# 32m1-ssm.net
KiCad netlist of a schematic drawn in Altium Designer
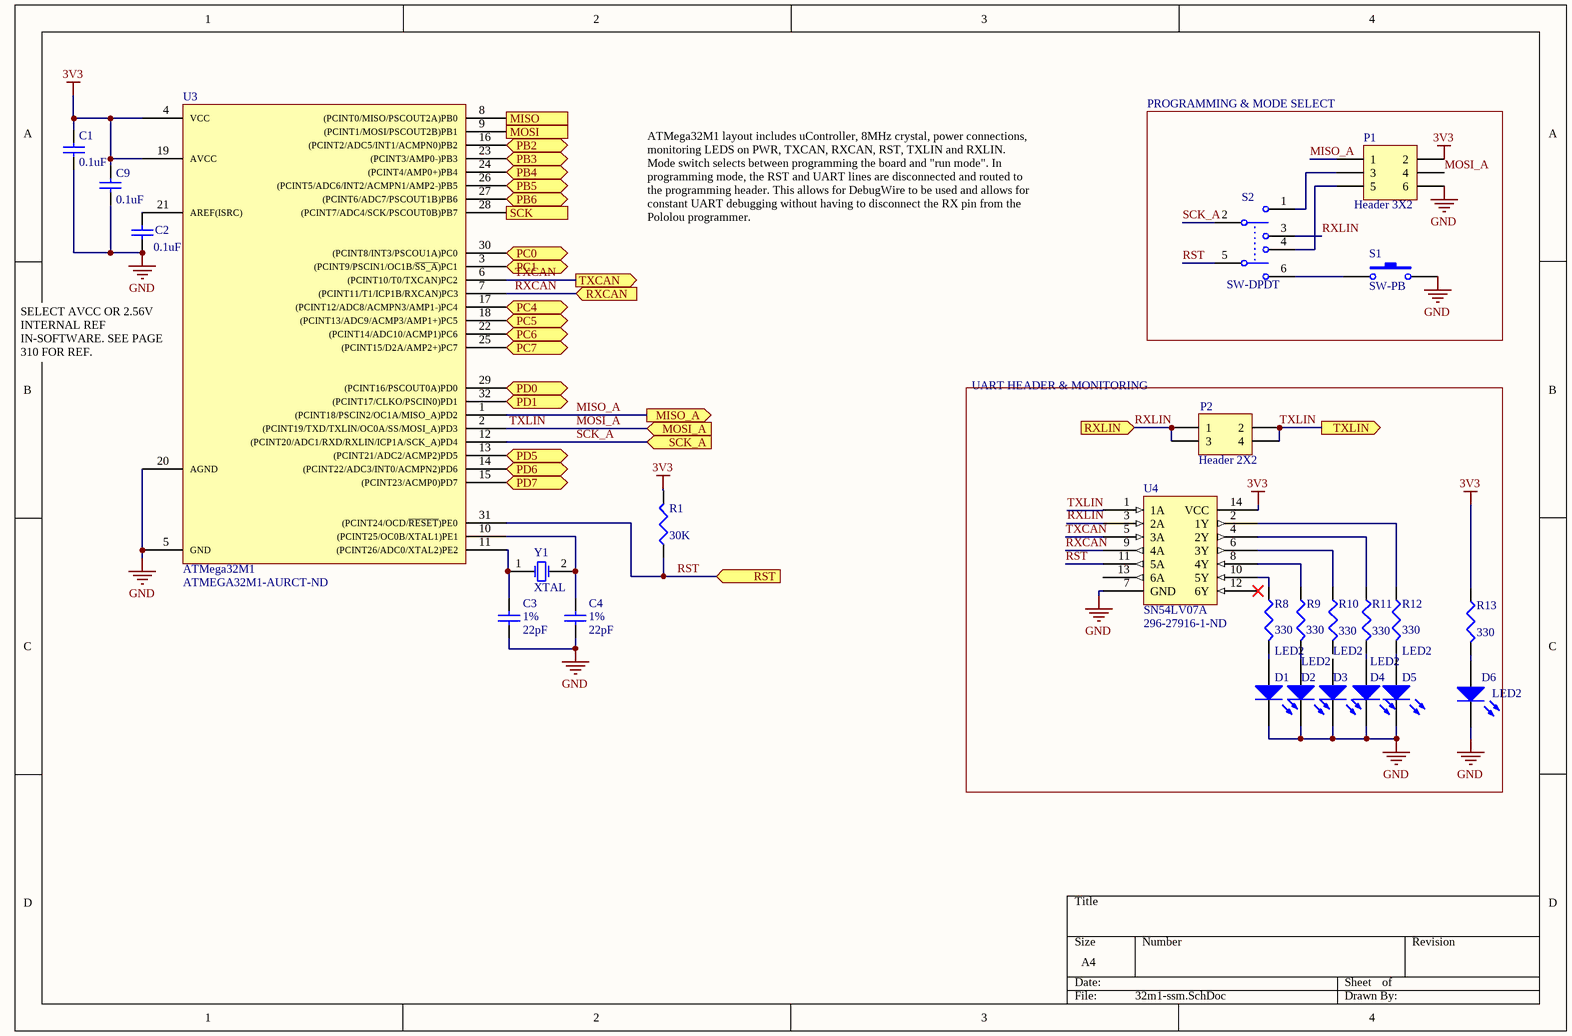
[diagram p0: 32m1-ssm.SchDoc]

(export (version "E")
  (design (tool "Eeschema 10.0.6"))
  (components
    (comp (ref "C1")
      (value "0.1uF")
      (footprint "C1206")
      (description "Capacitor (Semiconductor SIM Model)")
      (fields (field (name "Comment") "Cap Semi") (field (name "PUBLISHER") "Altium Limited"))
      (libsource (lib "Miscellaneous Devices") (part "Cap Semi"))
    )
    (comp (ref "C2")
      (value "0.1uF")
      (footprint "C1206")
      (description "Capacitor (Semiconductor SIM Model)")
      (fields (field (name "Comment") "Cap Semi") (field (name "PUBLISHER") "Altium Limited"))
      (libsource (lib "Miscellaneous Devices") (part "Cap Semi"))
    )
    (comp (ref "C3")
      (value "1%")
      (footprint "C1206")
      (description "Capacitor (Semiconductor SIM Model)")
      (fields (field (name "ALTIUM_VALUE") "22pF") (field (name "PUBLISHER") "Altium Limited"))
      (libsource (lib "Miscellaneous Devices") (part "Cap Semi"))
    )
    (comp (ref "C4")
      (value "1%")
      (footprint "C1206")
      (description "Capacitor (Semiconductor SIM Model)")
      (fields (field (name "ALTIUM_VALUE") "22pF") (field (name "PUBLISHER") "Altium Limited"))
      (libsource (lib "Miscellaneous Devices") (part "Cap Semi"))
    )
    (comp (ref "C9")
      (value "0.1uF")
      (footprint "C1206")
      (description "Capacitor (Semiconductor SIM Model)")
      (fields (field (name "Comment") "Cap Semi") (field (name "PUBLISHER") "Altium Limited"))
      (libsource (lib "Miscellaneous Devices") (part "Cap Semi"))
    )
    (comp (ref "D1")
      (value "LED2")
      (footprint "3.2X1.6X1.1")
      (description "Typical RED, GREEN, YELLOW, AMBER GaAs LED")
      (fields (field (name "PUBLISHER") "Altium Limited"))
      (libsource (lib "Miscellaneous Devices") (part "LED2"))
    )
    (comp (ref "D2")
      (value "LED2")
      (footprint "3.2X1.6X1.1")
      (description "Typical RED, GREEN, YELLOW, AMBER GaAs LED")
      (fields (field (name "PUBLISHER") "Altium Limited"))
      (libsource (lib "Miscellaneous Devices") (part "LED2"))
    )
    (comp (ref "D3")
      (value "LED2")
      (footprint "3.2X1.6X1.1")
      (description "Typical RED, GREEN, YELLOW, AMBER GaAs LED")
      (fields (field (name "PUBLISHER") "Altium Limited"))
      (libsource (lib "Miscellaneous Devices") (part "LED2"))
    )
    (comp (ref "D4")
      (value "LED2")
      (footprint "3.2X1.6X1.1")
      (description "Typical RED, GREEN, YELLOW, AMBER GaAs LED")
      (fields (field (name "PUBLISHER") "Altium Limited"))
      (libsource (lib "Miscellaneous Devices") (part "LED2"))
    )
    (comp (ref "D5")
      (value "LED2")
      (footprint "3.2X1.6X1.1")
      (description "Typical RED, GREEN, YELLOW, AMBER GaAs LED")
      (fields (field (name "PUBLISHER") "Altium Limited"))
      (libsource (lib "Miscellaneous Devices") (part "LED2"))
    )
    (comp (ref "D6")
      (value "LED2")
      (footprint "3.2X1.6X1.1")
      (description "Typical RED, GREEN, YELLOW, AMBER GaAs LED")
      (fields (field (name "PUBLISHER") "Altium Limited"))
      (libsource (lib "Miscellaneous Devices") (part "LED2"))
    )
    (comp (ref "P1")
      (value "Header 3X2")
      (footprint "HDR2X3")
      (description "Header, 3-Pin, Dual row")
      (fields (field (name "PUBLISHER") "Altium Limited"))
      (libsource (lib "Miscellaneous Connectors") (part "Header 3X2"))
    )
    (comp (ref "P2")
      (value "Header 2X2")
      (footprint "HDR2X2")
      (description "Header, 2-Pin, Dual row")
      (fields (field (name "PUBLISHER") "Altium Limited"))
      (libsource (lib "Miscellaneous Connectors") (part "Header 2X2"))
    )
    (comp (ref "R1")
      (value "30K")
      (footprint "J1-0603")
      (description "Resistor")
      (fields (field (name "Comment") "Res3") (field (name "PUBLISHER") "Altium Limited"))
      (libsource (lib "Miscellaneous Devices") (part "Res3"))
    )
    (comp (ref "R8")
      (value "330")
      (footprint "J1-0603")
      (description "Resistor")
      (fields (field (name "Comment") "Res3") (field (name "PUBLISHER") "Altium Limited"))
      (libsource (lib "Miscellaneous Devices") (part "Res3"))
    )
    (comp (ref "R9")
      (value "330")
      (footprint "J1-0603")
      (description "Resistor")
      (fields (field (name "Comment") "Res3") (field (name "PUBLISHER") "Altium Limited"))
      (libsource (lib "Miscellaneous Devices") (part "Res3"))
    )
    (comp (ref "R10")
      (value "330")
      (footprint "J1-0603")
      (description "Resistor")
      (fields (field (name "Comment") "Res3") (field (name "PUBLISHER") "Altium Limited"))
      (libsource (lib "Miscellaneous Devices") (part "Res3"))
    )
    (comp (ref "R11")
      (value "330")
      (footprint "J1-0603")
      (description "Resistor")
      (fields (field (name "Comment") "Res3") (field (name "PUBLISHER") "Altium Limited"))
      (libsource (lib "Miscellaneous Devices") (part "Res3"))
    )
    (comp (ref "R12")
      (value "330")
      (footprint "J1-0603")
      (description "Resistor")
      (fields (field (name "Comment") "Res3") (field (name "PUBLISHER") "Altium Limited"))
      (libsource (lib "Miscellaneous Devices") (part "Res3"))
    )
    (comp (ref "R13")
      (value "330")
      (footprint "J1-0603")
      (description "Resistor")
      (fields (field (name "Comment") "Res3") (field (name "PUBLISHER") "Altium Limited"))
      (libsource (lib "Miscellaneous Devices") (part "Res3"))
    )
    (comp (ref "S1")
      (value "SW-PB")
      (footprint "SPST-2")
      (description "Switch")
      (fields (field (name "PUBLISHER") "Altium Limited"))
      (libsource (lib "Miscellaneous Devices") (part "SW-PB"))
    )
    (comp (ref "S2")
      (value "SW-DPDT")
      (footprint "PCBComponent_1")
      (description "Double-Pole, Double-Throw Switch")
      (fields (field (name "PUBLISHER") "Altium Limited"))
      (libsource (lib "Miscellaneous Devices") (part "SW-DPDT"))
    )
    (comp (ref "U3")
      (value "ATMega32M1")
      (footprint "QFP80P900X900X120-32N")
      (description "Atmel 8-bit AVR microcontroller.")
      (fields (field (name "SUPPLIER PART NUMBER 1") "ATMEGA32M1-AURCT-ND"))
      (libsource (lib "ICs") (part "ATMega32M1"))
    )
    (comp (ref "U4")
      (value "SN54LV07A")
      (footprint "SOT402-1_N")
      (description "Six element 1-bit non-inverting open-drain buffer.")
      (fields (field (name "SUPPLIER PART NUMBER") "296-27916-1-ND"))
      (libsource (lib "ICs") (part "SN54LV07A"))
    )
    (comp (ref "Y1")
      (value "XTAL")
      (footprint "R38")
      (description "Crystal Oscillator")
      (fields (field (name "PUBLISHER") "Altium Limited"))
      (libsource (lib "Miscellaneous Devices") (part "XTAL"))
    )
  )
  (nets
    (net (code "1") (name "/MISO") (class "Default")
      (node (ref "U3") (pin "8") (pinfunction "(PCINT0/MISO/PSCOUT2A)PB0_8") (pintype "passive"))
    )
    (net (code "2") (name "/MISO_A") (class "Default")
      (node (ref "P1") (pin "1") (pinfunction "1_1") (pintype "passive"))
      (node (ref "U3") (pin "1") (pinfunction "(PCINT18/PSCIN2/OC1A/MISO_A)PD2_1") (pintype "passive"))
    )
    (net (code "3") (name "/MOSI") (class "Default")
      (node (ref "U3") (pin "9") (pinfunction "(PCINT1/MOSI/PSCOUT2B)PB1_9") (pintype "passive"))
    )
    (net (code "4") (name "/MOSI_A") (class "Default")
      (node (ref "P1") (pin "4") (pinfunction "4_4") (pintype "passive"))
      (node (ref "P2") (pin "2") (pinfunction "2_2") (pintype "passive"))
      (node (ref "P2") (pin "4") (pinfunction "4_4") (pintype "passive"))
      (node (ref "U3") (pin "2") (pinfunction "(PCINT19/TXD/TXLIN/OC0A/SS/MOSI_A)PD3_2") (pintype "passive"))
      (node (ref "U4") (pin "1") (pinfunction "1A_1") (pintype "input"))
    )
    (net (code "5") (name "/PB2") (class "Default")
      (node (ref "U3") (pin "16") (pinfunction "(PCINT2/ADC5/INT1/ACMPN0)PB2_16") (pintype "passive"))
    )
    (net (code "6") (name "/PB3") (class "Default")
      (node (ref "U3") (pin "23") (pinfunction "(PCINT3/AMP0-)PB3_23") (pintype "passive"))
    )
    (net (code "7") (name "/PB4") (class "Default")
      (node (ref "U3") (pin "24") (pinfunction "(PCINT4/AMP0+)PB4_24") (pintype "passive"))
    )
    (net (code "8") (name "/PB5") (class "Default")
      (node (ref "U3") (pin "26") (pinfunction "(PCINT5/ADC6/INT2/ACMPN1/AMP2-)PB5_26") (pintype "passive"))
    )
    (net (code "9") (name "/PB6") (class "Default")
      (node (ref "U3") (pin "27") (pinfunction "(PCINT6/ADC7/PSCOUT1B)PB6_27") (pintype "passive"))
    )
    (net (code "10") (name "/PC0") (class "Default")
      (node (ref "U3") (pin "30") (pinfunction "(PCINT8/INT3/PSCOU1A)PC0_30") (pintype "passive"))
    )
    (net (code "11") (name "/PC1") (class "Default")
      (node (ref "U3") (pin "3") (pinfunction "(PCINT9/PSCIN1/OC1B/~{SS_A})PC1_3") (pintype "passive"))
    )
    (net (code "12") (name "/PC4") (class "Default")
      (node (ref "U3") (pin "17") (pinfunction "(PCINT12/ADC8/ACMPN3/AMP1-)PC4_17") (pintype "passive"))
    )
    (net (code "13") (name "/PC5") (class "Default")
      (node (ref "U3") (pin "18") (pinfunction "(PCINT13/ADC9/ACMP3/AMP1+)PC5_18") (pintype "passive"))
    )
    (net (code "14") (name "/PC6") (class "Default")
      (node (ref "U3") (pin "22") (pinfunction "(PCINT14/ADC10/ACMP1)PC6_22") (pintype "passive"))
    )
    (net (code "15") (name "/PC7") (class "Default")
      (node (ref "U3") (pin "25") (pinfunction "(PCINT15/D2A/AMP2+)PC7_25") (pintype "passive"))
    )
    (net (code "16") (name "/PD0") (class "Default")
      (node (ref "U3") (pin "29") (pinfunction "(PCINT16/PSCOUT0A)PD0_29") (pintype "passive"))
    )
    (net (code "17") (name "/PD1") (class "Default")
      (node (ref "U3") (pin "32") (pinfunction "(PCINT17/CLKO/PSCIN0)PD1_32") (pintype "passive"))
    )
    (net (code "18") (name "/PD5") (class "Default")
      (node (ref "U3") (pin "13") (pinfunction "(PCINT21/ADC2/ACMP2)PD5_13") (pintype "passive"))
    )
    (net (code "19") (name "/PD6") (class "Default")
      (node (ref "U3") (pin "14") (pinfunction "(PCINT22/ADC3/INT0/ACMPN2)PD6_14") (pintype "passive"))
    )
    (net (code "20") (name "/PD7") (class "Default")
      (node (ref "U3") (pin "15") (pinfunction "(PCINT23/ACMP0)PD7_15") (pintype "passive"))
    )
    (net (code "21") (name "/RST") (class "Default")
      (node (ref "R1") (pin "1") (pinfunction "1_1") (pintype "passive"))
      (node (ref "S2") (pin "5") (pinfunction "5_5") (pintype "passive"))
      (node (ref "U3") (pin "31") (pinfunction "(PCINT24/OCD/~{RESET})PE0_31") (pintype "passive"))
      (node (ref "U4") (pin "11") (pinfunction "5A_11") (pintype "output"))
    )
    (net (code "22") (name "/RXCAN") (class "Default")
      (node (ref "U3") (pin "7") (pinfunction "(PCINT11/T1/ICP1B/RXCAN)PC3_7") (pintype "passive"))
      (node (ref "U4") (pin "9") (pinfunction "4A_9") (pintype "output"))
    )
    (net (code "23") (name "/RXLIN") (class "Default")
      (node (ref "P2") (pin "1") (pinfunction "1_1") (pintype "passive"))
      (node (ref "P2") (pin "3") (pinfunction "3_3") (pintype "passive"))
      (node (ref "S2") (pin "3") (pinfunction "3_3") (pintype "passive"))
      (node (ref "U4") (pin "3") (pinfunction "2A_3") (pintype "input"))
    )
    (net (code "24") (name "/SCK") (class "Default")
      (node (ref "U3") (pin "28") (pinfunction "(PCINT7/ADC4/SCK/PSCOUT0B)PB7_28") (pintype "passive"))
    )
    (net (code "25") (name "/SCK_A") (class "Default")
      (node (ref "S2") (pin "2") (pinfunction "2_2") (pintype "passive"))
      (node (ref "U3") (pin "12") (pinfunction "(PCINT20/ADC1/RXD/RXLIN/ICP1A/SCK_A)PD4_12") (pintype "passive"))
    )
    (net (code "26") (name "/TXCAN") (class "Default")
      (node (ref "U3") (pin "6") (pinfunction "(PCINT10/T0/TXCAN)PC2_6") (pintype "passive"))
      (node (ref "U4") (pin "5") (pinfunction "3A_5") (pintype "input"))
    )
    (net (code "27") (name "3V3") (class "Default")
      (node (ref "C1") (pin "2") (pinfunction "2_2") (pintype "passive"))
      (node (ref "C9") (pin "2") (pinfunction "2_2") (pintype "passive"))
      (node (ref "P1") (pin "2") (pinfunction "2_2") (pintype "passive"))
      (node (ref "R1") (pin "2") (pinfunction "2_2") (pintype "passive"))
      (node (ref "R13") (pin "1") (pinfunction "1_1") (pintype "passive"))
      (node (ref "U3") (pin "19") (pinfunction "AVCC_19") (pintype "passive"))
      (node (ref "U3") (pin "4") (pinfunction "VCC_4") (pintype "passive"))
      (node (ref "U4") (pin "14") (pinfunction "VCC_14") (pintype "power_in"))
    )
    (net (code "28") (name "GND") (class "Default")
      (node (ref "C1") (pin "1") (pinfunction "1_1") (pintype "passive"))
      (node (ref "C2") (pin "2") (pinfunction "2_2") (pintype "passive"))
      (node (ref "C3") (pin "1") (pinfunction "1_1") (pintype "passive"))
      (node (ref "C4") (pin "1") (pinfunction "1_1") (pintype "passive"))
      (node (ref "C9") (pin "1") (pinfunction "1_1") (pintype "passive"))
      (node (ref "D1") (pin "2") (pinfunction "K_2") (pintype "passive"))
      (node (ref "D2") (pin "2") (pinfunction "K_2") (pintype "passive"))
      (node (ref "D3") (pin "2") (pinfunction "K_2") (pintype "passive"))
      (node (ref "D4") (pin "2") (pinfunction "K_2") (pintype "passive"))
      (node (ref "D5") (pin "2") (pinfunction "K_2") (pintype "passive"))
      (node (ref "D6") (pin "2") (pinfunction "K_2") (pintype "passive"))
      (node (ref "P1") (pin "6") (pinfunction "6_6") (pintype "passive"))
      (node (ref "S1") (pin "2") (pinfunction "2_2") (pintype "passive"))
      (node (ref "U3") (pin "20") (pinfunction "AGND_20") (pintype "passive"))
      (node (ref "U3") (pin "5") (pinfunction "GND_5") (pintype "passive"))
      (node (ref "U4") (pin "7") (pinfunction "GND_7") (pintype "power_in"))
    )
    (net (code "29") (name "Net-(D1-A)") (class "Default")
      (node (ref "D1") (pin "1") (pinfunction "A_1") (pintype "passive"))
      (node (ref "R8") (pin "2") (pinfunction "2_2") (pintype "passive"))
    )
    (net (code "30") (name "Net-(D2-A)") (class "Default")
      (node (ref "D2") (pin "1") (pinfunction "A_1") (pintype "passive"))
      (node (ref "R9") (pin "2") (pinfunction "2_2") (pintype "passive"))
    )
    (net (code "31") (name "Net-(D4-A)") (class "Default")
      (node (ref "D4") (pin "1") (pinfunction "A_1") (pintype "passive"))
      (node (ref "R11") (pin "2") (pinfunction "2_2") (pintype "passive"))
    )
    (net (code "32") (name "Net-(D5-A)") (class "Default")
      (node (ref "D5") (pin "1") (pinfunction "A_1") (pintype "passive"))
      (node (ref "R12") (pin "2") (pinfunction "2_2") (pintype "passive"))
    )
    (net (code "33") (name "Net-(D6-A)") (class "Default")
      (node (ref "D6") (pin "1") (pinfunction "A_1") (pintype "passive"))
      (node (ref "R13") (pin "2") (pinfunction "2_2") (pintype "passive"))
    )
    (net (code "34") (name "Net-(P1-Pad3)") (class "Default")
      (node (ref "P1") (pin "3") (pinfunction "3_3") (pintype "passive"))
      (node (ref "S2") (pin "1") (pinfunction "1_1") (pintype "passive"))
    )
    (net (code "35") (name "Net-(P1-Pad5)") (class "Default")
      (node (ref "P1") (pin "5") (pinfunction "5_5") (pintype "passive"))
      (node (ref "S2") (pin "4") (pinfunction "4_4") (pintype "passive"))
    )
    (net (code "36") (name "Net-(S1-Pad1)") (class "Default")
      (node (ref "S1") (pin "1") (pinfunction "1_1") (pintype "passive"))
      (node (ref "S2") (pin "6") (pinfunction "6_6") (pintype "passive"))
    )
    (net (code "37") (name "Net-(U3-(PCINT25{slash}OC0B{slash}XTAL1)PE1)") (class "Default")
      (node (ref "C4") (pin "2") (pinfunction "2_2") (pintype "passive"))
      (node (ref "U3") (pin "10") (pinfunction "(PCINT25/OC0B/XTAL1)PE1_10") (pintype "passive"))
      (node (ref "Y1") (pin "2") (pinfunction "OSC2_2") (pintype "passive"))
    )
    (net (code "38") (name "Net-(U3-(PCINT26{slash}ADC0{slash}XTAL2)PE2)") (class "Default")
      (node (ref "C3") (pin "2") (pinfunction "2_2") (pintype "passive"))
      (node (ref "U3") (pin "11") (pinfunction "(PCINT26/ADC0/XTAL2)PE2_11") (pintype "passive"))
      (node (ref "Y1") (pin "1") (pinfunction "OSC1_1") (pintype "passive"))
    )
    (net (code "39") (name "Net-(U3-AREF(ISRC))") (class "Default")
      (node (ref "C2") (pin "1") (pinfunction "1_1") (pintype "passive"))
      (node (ref "U3") (pin "21") (pinfunction "AREF(ISRC)_21") (pintype "passive"))
    )
    (net (code "40") (name "Net-(U4-1Y)") (class "Default")
      (node (ref "R12") (pin "1") (pinfunction "1_1") (pintype "passive"))
      (node (ref "U4") (pin "2") (pinfunction "1Y_2") (pintype "output"))
    )
    (net (code "41") (name "Net-(U4-2Y)") (class "Default")
      (node (ref "R11") (pin "1") (pinfunction "1_1") (pintype "passive"))
      (node (ref "U4") (pin "4") (pinfunction "2Y_4") (pintype "output"))
    )
    (net (code "42") (name "Net-(U4-3Y)") (class "Default")
      (node (ref "R10") (pin "1") (pinfunction "1_1") (pintype "passive"))
      (node (ref "U4") (pin "6") (pinfunction "3Y_6") (pintype "output"))
    )
    (net (code "43") (name "Net-(U4-4Y)") (class "Default")
      (node (ref "R9") (pin "1") (pinfunction "1_1") (pintype "passive"))
      (node (ref "U4") (pin "8") (pinfunction "4Y_8") (pintype "input"))
    )
    (net (code "44") (name "Net-(U4-5Y)") (class "Default")
      (node (ref "R8") (pin "1") (pinfunction "1_1") (pintype "passive"))
      (node (ref "U4") (pin "10") (pinfunction "5Y_10") (pintype "input"))
    )
    (net (code "45") (name "unconnected-(D3-A-Pad1)") (class "Default")
      (node (ref "D3") (pin "1") (pinfunction "A_1") (pintype "passive"))
    )
    (net (code "46") (name "unconnected-(R10-Pad2)") (class "Default")
      (node (ref "R10") (pin "2") (pinfunction "2_2") (pintype "passive"))
    )
    (net (code "47") (name "unconnected-(U4-6A-Pad13)") (class "Default")
      (node (ref "U4") (pin "13") (pinfunction "6A_13") (pintype "output"))
    )
    (net (code "48") (name "unconnected-(U4-6Y-Pad12)") (class "Default")
      (node (ref "U4") (pin "12") (pinfunction "6Y_12") (pintype "input+no_connect"))
    )
  )
)
